# supply2.net
KiCad netlist of a schematic drawn in Altium Designer
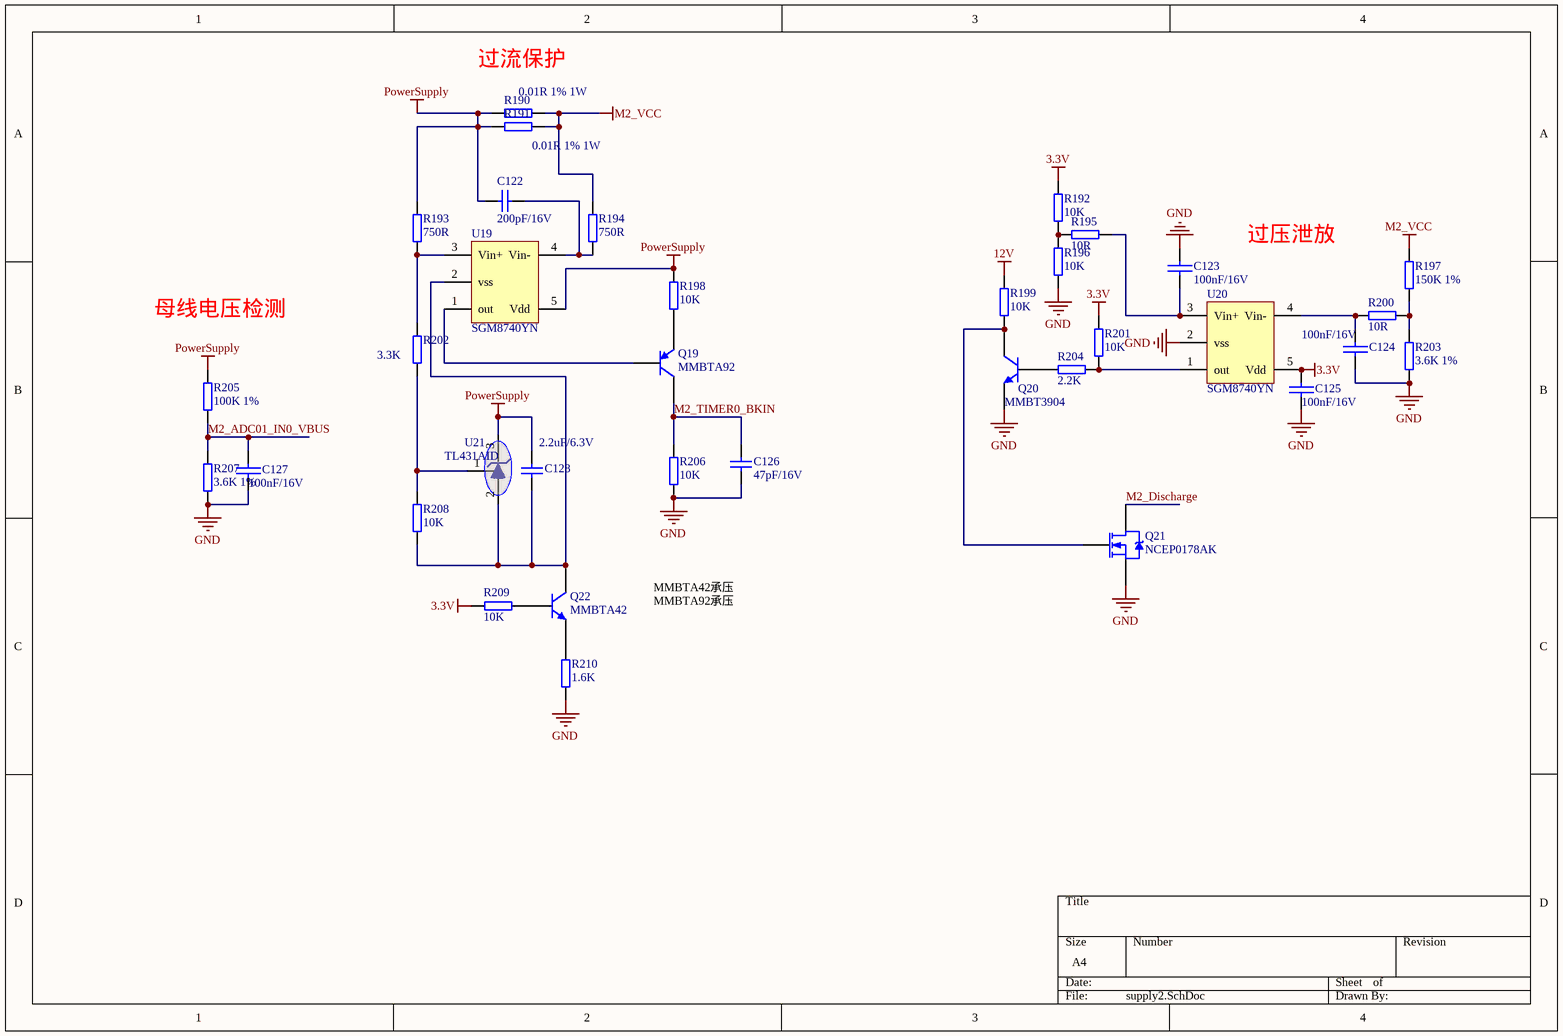
[diagram p0: supply2.SchDoc]

(export (version "E")
  (design (tool "Eeschema 10.0.6"))
  (components
    (comp (ref "C122") (value "200pF/16V") (footprint "C0402") (libsource (lib "zijianku") (part "cap")))
    (comp (ref "C123")
      (value "100nF/16V")
      (footprint "C0402")
      (description "Capacitor")
      (libsource (lib "*") (part "CAP"))
    )
    (comp (ref "C124")
      (value "100nF/16V")
      (footprint "C0402")
      (description "Capacitor")
      (libsource (lib "*") (part "CAP"))
    )
    (comp (ref "C125")
      (value "100nF/16V")
      (footprint "C0402")
      (description "Capacitor")
      (libsource (lib "*") (part "CAP"))
    )
    (comp (ref "C126") (value "47pF/16V") (footprint "C0402") (libsource (lib "zijianku") (part "cap")))
    (comp (ref "C127")
      (value "100nF/16V")
      (footprint "C0402")
      (description "Capacitor")
      (libsource (lib "*") (part "CAP"))
    )
    (comp (ref "C128") (value "2.2uF/6.3V") (footprint "C0402") (libsource (lib "zijianku") (part "cap")))
    (comp (ref "Q19") (value "MMBTA92") (footprint "SOT-23") (libsource (lib "zijianku") (part "PNP")))
    (comp (ref "Q20") (value "MMBT3904") (footprint "SOT-23") (libsource (lib "zijianku") (part "NPN")))
    (comp (ref "Q21")
      (value "NCEP0178AK")
      (footprint "D-PAK(TO-252AA)")
      (libsource (lib "zijianku") (part "N-channel Enhancement MOS"))
    )
    (comp (ref "Q22") (value "MMBTA42") (footprint "SOT-23") (libsource (lib "zijianku") (part "NPN")))
    (comp (ref "R190")
      (value "0.01R 1% 1W")
      (footprint "R1210")
      (libsource (lib "zijianku") (part "Resistance"))
    )
    (comp (ref "R191")
      (value "0.01R 1% 1W")
      (footprint "R1210")
      (libsource (lib "zijianku") (part "Resistance"))
    )
    (comp (ref "R192") (value "10K") (footprint "R0402") (libsource (lib "zijianku") (part "Resistance")))
    (comp (ref "R193") (value "750R") (footprint "R0402") (libsource (lib "zijianku") (part "Resistance")))
    (comp (ref "R194") (value "750R") (footprint "R0402") (libsource (lib "zijianku") (part "Resistance")))
    (comp (ref "R195") (value "10R") (footprint "R0402") (libsource (lib "zijianku") (part "Resistance")))
    (comp (ref "R196") (value "10K") (footprint "R0402") (libsource (lib "zijianku") (part "Resistance")))
    (comp (ref "R197") (value "150K 1%") (footprint "R0603") (libsource (lib "zijianku") (part "Resistance")))
    (comp (ref "R198") (value "10K") (footprint "R0402") (libsource (lib "zijianku") (part "Resistance")))
    (comp (ref "R199") (value "10K") (footprint "R0402") (libsource (lib "zijianku") (part "Resistance")))
    (comp (ref "R200") (value "10R") (footprint "R0402") (libsource (lib "zijianku") (part "Resistance")))
    (comp (ref "R201") (value "10K") (footprint "R0402") (libsource (lib "zijianku") (part "Resistance")))
    (comp (ref "R202") (value "3.3K") (footprint "R0402") (libsource (lib "zijianku") (part "Resistance")))
    (comp (ref "R203") (value "3.6K 1%") (footprint "R0603") (libsource (lib "zijianku") (part "Resistance")))
    (comp (ref "R204") (value "2.2K") (footprint "R0402") (libsource (lib "zijianku") (part "Resistance")))
    (comp (ref "R205") (value "100K 1%") (footprint "R0603") (libsource (lib "zijianku") (part "Resistance")))
    (comp (ref "R206") (value "10K") (footprint "R0402") (libsource (lib "zijianku") (part "Resistance")))
    (comp (ref "R207") (value "3.6K 1%") (footprint "R0603") (libsource (lib "zijianku") (part "Resistance")))
    (comp (ref "R208") (value "10K") (footprint "R0402") (libsource (lib "zijianku") (part "Resistance")))
    (comp (ref "R209") (value "10K") (footprint "R0402") (libsource (lib "zijianku") (part "Resistance")))
    (comp (ref "R210") (value "1.6K") (footprint "R0402") (libsource (lib "zijianku") (part "Resistance")))
    (comp (ref "U19")
      (value "SGM8740YN")
      (footprint "SOT-23(5)")
      (description "圣邦微电子 丝印 SL5XX")
      (libsource (lib "Common Device") (part "LMV7239"))
    )
    (comp (ref "U20")
      (value "SGM8740YN")
      (footprint "SOT-23(5)")
      (description "圣邦微电子 丝印 SL5XX")
      (libsource (lib "Common Device") (part "LMV7239"))
    )
    (comp (ref "U21")
      (value "TL431AID")
      (footprint "SOT-23")
      (description "注意引脚关系：1-C 2-R 3-A")
      (libsource (lib "Common Power") (part "TL431"))
    )
  )
  (nets
    (net (code "1") (name "/M2_ADC01_IN0_VBUS") (class "Default")
      (node (ref "C127") (pin "1") (pinfunction "1_1") (pintype "passive"))
      (node (ref "R205") (pin "1") (pintype "passive"))
      (node (ref "R207") (pin "2") (pintype "passive"))
    )
    (net (code "2") (name "/M2_Discharge") (class "Default")
      (node (ref "Q21") (pin "3") (pinfunction "D_3") (pintype "passive"))
    )
    (net (code "3") (name "/M2_TIMER0_BKIN") (class "Default")
      (node (ref "C126") (pin "1") (pinfunction "0_1") (pintype "passive"))
      (node (ref "Q19") (pin "3") (pinfunction "C_3") (pintype "passive"))
      (node (ref "R206") (pin "2") (pintype "passive"))
    )
    (net (code "4") (name "3.3V") (class "Default")
      (node (ref "C125") (pin "1") (pinfunction "1_1") (pintype "passive"))
      (node (ref "R192") (pin "2") (pintype "passive"))
      (node (ref "R201") (pin "2") (pintype "passive"))
      (node (ref "R209") (pin "1") (pintype "passive"))
      (node (ref "U20") (pin "5") (pinfunction "Vdd_5") (pintype "passive"))
    )
    (net (code "5") (name "12V") (class "Default") (node (ref "R199") (pin "2") (pintype "passive")))
    (net (code "6") (name "GND") (class "Default")
      (node (ref "C123") (pin "2") (pinfunction "2_2") (pintype "passive"))
      (node (ref "C124") (pin "2") (pinfunction "2_2") (pintype "passive"))
      (node (ref "C125") (pin "2") (pinfunction "2_2") (pintype "passive"))
      (node (ref "C126") (pin "2") (pinfunction "1_2") (pintype "passive"))
      (node (ref "C127") (pin "2") (pinfunction "2_2") (pintype "passive"))
      (node (ref "Q20") (pin "2") (pinfunction "E_2") (pintype "passive"))
      (node (ref "Q21") (pin "2") (pinfunction "S_2") (pintype "passive"))
      (node (ref "R196") (pin "1") (pintype "passive"))
      (node (ref "R203") (pin "1") (pintype "passive"))
      (node (ref "R206") (pin "1") (pintype "passive"))
      (node (ref "R207") (pin "1") (pintype "passive"))
      (node (ref "R210") (pin "1") (pintype "passive"))
      (node (ref "U20") (pin "2") (pinfunction "vss_2") (pintype "passive"))
    )
    (net (code "7") (name "M2_VCC") (class "Default")
      (node (ref "R190") (pin "1") (pintype "passive"))
      (node (ref "R191") (pin "1") (pintype "passive"))
      (node (ref "R194") (pin "2") (pintype "passive"))
      (node (ref "R197") (pin "2") (pintype "passive"))
    )
    (net (code "8") (name "Net-(C122-0)") (class "Default")
      (node (ref "C122") (pin "1") (pinfunction "0_1") (pintype "passive"))
      (node (ref "R194") (pin "1") (pintype "passive"))
      (node (ref "U19") (pin "4") (pinfunction "Vin-_4") (pintype "passive"))
    )
    (net (code "9") (name "Net-(C128-1)") (class "Default")
      (node (ref "C128") (pin "2") (pinfunction "1_2") (pintype "passive"))
      (node (ref "Q22") (pin "3") (pinfunction "C_3") (pintype "passive"))
      (node (ref "R208") (pin "2") (pintype "passive"))
      (node (ref "U19") (pin "2") (pinfunction "vss_2") (pintype "passive"))
      (node (ref "U21") (pin "2") (pinfunction "A_2") (pintype "passive"))
    )
    (net (code "10") (name "Net-(Q19-B)") (class "Default")
      (node (ref "Q19") (pin "1") (pinfunction "B_1") (pintype "passive"))
      (node (ref "U19") (pin "1") (pinfunction "out_1") (pintype "passive"))
    )
    (net (code "11") (name "Net-(Q19-E)") (class "Default")
      (node (ref "Q19") (pin "2") (pinfunction "E_2") (pintype "passive"))
      (node (ref "R198") (pin "1") (pintype "passive"))
    )
    (net (code "12") (name "Net-(Q20-B)") (class "Default")
      (node (ref "Q20") (pin "1") (pinfunction "B_1") (pintype "passive"))
      (node (ref "R204") (pin "1") (pintype "passive"))
    )
    (net (code "13") (name "Net-(Q20-C)") (class "Default")
      (node (ref "Q20") (pin "3") (pinfunction "C_3") (pintype "passive"))
      (node (ref "Q21") (pin "1") (pinfunction "G_1") (pintype "passive"))
      (node (ref "R199") (pin "1") (pintype "passive"))
    )
    (net (code "14") (name "Net-(Q22-B)") (class "Default")
      (node (ref "Q22") (pin "1") (pinfunction "B_1") (pintype "passive"))
      (node (ref "R209") (pin "2") (pintype "passive"))
    )
    (net (code "15") (name "Net-(Q22-E)") (class "Default")
      (node (ref "Q22") (pin "2") (pinfunction "E_2") (pintype "passive"))
      (node (ref "R210") (pin "2") (pintype "passive"))
    )
    (net (code "16") (name "Net-(R192-Pad1)") (class "Default")
      (node (ref "R192") (pin "1") (pintype "passive"))
      (node (ref "R195") (pin "2") (pintype "passive"))
      (node (ref "R196") (pin "2") (pintype "passive"))
    )
    (net (code "17") (name "Net-(R197-Pad1)") (class "Default")
      (node (ref "R197") (pin "1") (pintype "passive"))
      (node (ref "R200") (pin "1") (pintype "passive"))
      (node (ref "R203") (pin "2") (pintype "passive"))
    )
    (net (code "18") (name "Net-(U19-Vin+)") (class "Default")
      (node (ref "R193") (pin "1") (pintype "passive"))
      (node (ref "R202") (pin "1") (pintype "passive"))
      (node (ref "U19") (pin "3") (pinfunction "Vin+_3") (pintype "passive"))
    )
    (net (code "19") (name "Net-(U20-Vin+)") (class "Default")
      (node (ref "C123") (pin "1") (pinfunction "1_1") (pintype "passive"))
      (node (ref "R195") (pin "1") (pintype "passive"))
      (node (ref "U20") (pin "3") (pinfunction "Vin+_3") (pintype "passive"))
    )
    (net (code "20") (name "Net-(U20-Vin-)") (class "Default")
      (node (ref "C124") (pin "1") (pinfunction "1_1") (pintype "passive"))
      (node (ref "R200") (pin "2") (pintype "passive"))
      (node (ref "U20") (pin "4") (pinfunction "Vin-_4") (pintype "passive"))
    )
    (net (code "21") (name "Net-(U20-out)") (class "Default")
      (node (ref "R201") (pin "1") (pintype "passive"))
      (node (ref "R204") (pin "2") (pintype "passive"))
      (node (ref "U20") (pin "1") (pinfunction "out_1") (pintype "passive"))
    )
    (net (code "22") (name "Net-(U21-REF)") (class "Default")
      (node (ref "R202") (pin "2") (pintype "passive"))
      (node (ref "R208") (pin "1") (pintype "passive"))
      (node (ref "U21") (pin "1") (pinfunction "REF_1") (pintype "passive"))
    )
    (net (code "23") (name "PowerSupply") (class "Default")
      (node (ref "C122") (pin "2") (pinfunction "1_2") (pintype "passive"))
      (node (ref "C128") (pin "1") (pinfunction "0_1") (pintype "passive"))
      (node (ref "R190") (pin "2") (pintype "passive"))
      (node (ref "R191") (pin "2") (pintype "passive"))
      (node (ref "R193") (pin "2") (pintype "passive"))
      (node (ref "R198") (pin "2") (pintype "passive"))
      (node (ref "R205") (pin "2") (pintype "passive"))
      (node (ref "U19") (pin "5") (pinfunction "Vdd_5") (pintype "passive"))
      (node (ref "U21") (pin "3") (pinfunction "K_3") (pintype "passive"))
    )
  )
)
